# SD_Card.net
KiCad netlist of a schematic drawn in Altium Designer
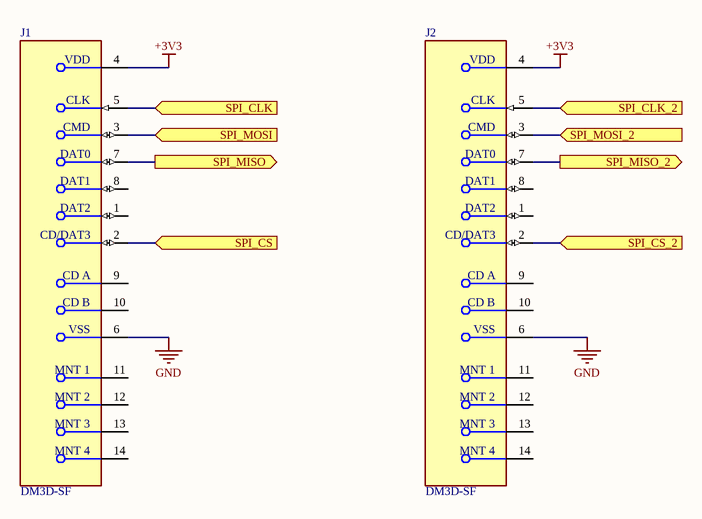
[diagram p0: SD_Card.SchDoc]

(export (version "E")
  (design (tool "Eeschema 10.0.6"))
  (components
    (comp (ref "J1")
      (value "DM3D-SF")
      (footprint "FP-DM3D-SF-MFG")
      (description "CONN MICRO SD CARD PUSH-PULL")
      (libsource (lib "Altium Content Vault") (part "375756fe1061de806c40c19e9001ea3"))
    )
    (comp (ref "J2")
      (value "DM3D-SF")
      (footprint "FP-DM3D-SF-MFG")
      (description "CONN MICRO SD CARD PUSH-PULL")
      (libsource (lib "Altium Content Vault") (part "375756fe1061de806c40c19e9001ea3"))
    )
  )
  (nets
    (net (code "1") (name "+3V3") (class "Default")
      (node (ref "J1") (pin "4") (pinfunction "VDD_4") (pintype "power_in"))
      (node (ref "J2") (pin "4") (pinfunction "VDD_4") (pintype "power_in"))
    )
    (net (code "2") (name "/SPI_CLK") (class "Default")
      (node (ref "J1") (pin "5") (pinfunction "CLK_5") (pintype "input"))
    )
    (net (code "3") (name "/SPI_CLK_2") (class "Default")
      (node (ref "J2") (pin "5") (pinfunction "CLK_5") (pintype "input"))
    )
    (net (code "4") (name "/SPI_CS") (class "Default")
      (node (ref "J1") (pin "2") (pinfunction "CD/DAT3_2") (pintype "bidirectional"))
    )
    (net (code "5") (name "/SPI_CS_2") (class "Default")
      (node (ref "J2") (pin "2") (pinfunction "CD/DAT3_2") (pintype "bidirectional"))
    )
    (net (code "6") (name "/SPI_MISO") (class "Default")
      (node (ref "J1") (pin "7") (pinfunction "DAT0_7") (pintype "bidirectional"))
    )
    (net (code "7") (name "/SPI_MISO_2") (class "Default")
      (node (ref "J2") (pin "7") (pinfunction "DAT0_7") (pintype "bidirectional"))
    )
    (net (code "8") (name "/SPI_MOSI") (class "Default")
      (node (ref "J1") (pin "3") (pinfunction "CMD_3") (pintype "bidirectional"))
    )
    (net (code "9") (name "/SPI_MOSI_2") (class "Default")
      (node (ref "J2") (pin "3") (pinfunction "CMD_3") (pintype "bidirectional"))
    )
    (net (code "10") (name "GND") (class "Default")
      (node (ref "J1") (pin "6") (pinfunction "VSS_6") (pintype "power_in"))
      (node (ref "J2") (pin "6") (pinfunction "VSS_6") (pintype "power_in"))
    )
    (net (code "11") (name "unconnected-(J1-CD_A-Pad9)") (class "Default")
      (node (ref "J1") (pin "9") (pinfunction "CD_A_9") (pintype "passive"))
    )
    (net (code "12") (name "unconnected-(J1-CD_B-Pad10)") (class "Default")
      (node (ref "J1") (pin "10") (pinfunction "CD_B_10") (pintype "passive"))
    )
    (net (code "13") (name "unconnected-(J1-DAT1-Pad8)") (class "Default")
      (node (ref "J1") (pin "8") (pinfunction "DAT1_8") (pintype "bidirectional"))
    )
    (net (code "14") (name "unconnected-(J1-DAT2-Pad1)") (class "Default")
      (node (ref "J1") (pin "1") (pinfunction "DAT2_1") (pintype "bidirectional"))
    )
    (net (code "15") (name "unconnected-(J1-MNT_1-Pad11)") (class "Default")
      (node (ref "J1") (pin "11") (pinfunction "MNT_1_11") (pintype "passive"))
    )
    (net (code "16") (name "unconnected-(J1-MNT_2-Pad12)") (class "Default")
      (node (ref "J1") (pin "12") (pinfunction "MNT_2_12") (pintype "passive"))
    )
    (net (code "17") (name "unconnected-(J1-MNT_3-Pad13)") (class "Default")
      (node (ref "J1") (pin "13") (pinfunction "MNT_3_13") (pintype "passive"))
    )
    (net (code "18") (name "unconnected-(J1-MNT_4-Pad14)") (class "Default")
      (node (ref "J1") (pin "14") (pinfunction "MNT_4_14") (pintype "passive"))
    )
    (net (code "19") (name "unconnected-(J2-CD_A-Pad9)") (class "Default")
      (node (ref "J2") (pin "9") (pinfunction "CD_A_9") (pintype "passive"))
    )
    (net (code "20") (name "unconnected-(J2-CD_B-Pad10)") (class "Default")
      (node (ref "J2") (pin "10") (pinfunction "CD_B_10") (pintype "passive"))
    )
    (net (code "21") (name "unconnected-(J2-DAT1-Pad8)") (class "Default")
      (node (ref "J2") (pin "8") (pinfunction "DAT1_8") (pintype "bidirectional"))
    )
    (net (code "22") (name "unconnected-(J2-DAT2-Pad1)") (class "Default")
      (node (ref "J2") (pin "1") (pinfunction "DAT2_1") (pintype "bidirectional"))
    )
    (net (code "23") (name "unconnected-(J2-MNT_1-Pad11)") (class "Default")
      (node (ref "J2") (pin "11") (pinfunction "MNT_1_11") (pintype "passive"))
    )
    (net (code "24") (name "unconnected-(J2-MNT_2-Pad12)") (class "Default")
      (node (ref "J2") (pin "12") (pinfunction "MNT_2_12") (pintype "passive"))
    )
    (net (code "25") (name "unconnected-(J2-MNT_3-Pad13)") (class "Default")
      (node (ref "J2") (pin "13") (pinfunction "MNT_3_13") (pintype "passive"))
    )
    (net (code "26") (name "unconnected-(J2-MNT_4-Pad14)") (class "Default")
      (node (ref "J2") (pin "14") (pinfunction "MNT_4_14") (pintype "passive"))
    )
  )
)
